# attiny85_transistor.net
KiCad netlist of a schematic drawn in EAGLE
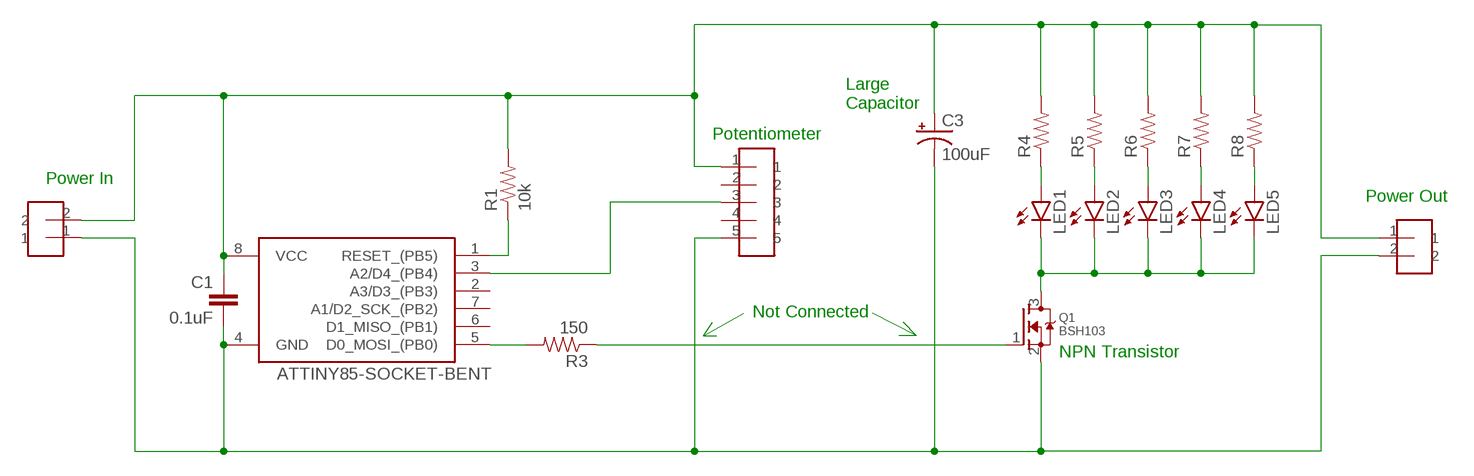
[diagram p0: schematic, sheet 1]

(export (version "E")
  (design (tool "Eeschema 10.0.6"))
  (components
    (comp (ref "C1")
      (value "0.1uF")
      (footprint "eagle-import:0805")
      (libsource (lib "eagle-import") (part "CAP-0805"))
    )
    (comp (ref "C3")
      (value "100uF")
      (footprint "eagle-import:PANASONIC_D")
      (libsource (lib "eagle-import") (part "CAP_POLD"))
    )
    (comp (ref "LED1")
      (value "LED0603")
      (footprint "eagle-import:LED-0603")
      (libsource (lib "eagle-import") (part "LED0603"))
    )
    (comp (ref "LED2")
      (value "LED0603")
      (footprint "eagle-import:LED-0603")
      (libsource (lib "eagle-import") (part "LED0603"))
    )
    (comp (ref "LED3")
      (value "LED0603")
      (footprint "eagle-import:LED-0603")
      (libsource (lib "eagle-import") (part "LED0603"))
    )
    (comp (ref "LED4")
      (value "LED0603")
      (footprint "eagle-import:LED-0603")
      (libsource (lib "eagle-import") (part "LED0603"))
    )
    (comp (ref "LED5")
      (value "LED0603")
      (footprint "eagle-import:LED-0603")
      (libsource (lib "eagle-import") (part "LED0603"))
    )
    (comp (ref "POTENTIOMETER")
      (value "HEADER-5")
      (footprint "eagle-import:HEADER-5")
      (libsource (lib "eagle-import") (part "HEADER-5"))
    )
    (comp (ref "Q1")
      (value "BSH103")
      (footprint "eagle-import:SOT23")
      (libsource (lib "eagle-import") (part "MOSFET-NREFLOW"))
    )
    (comp (ref "R1")
      (value "10k")
      (footprint "eagle-import:0805")
      (libsource (lib "eagle-import") (part "RESISTOR-0805"))
    )
    (comp (ref "R3")
      (value "150")
      (footprint "eagle-import:0805")
      (libsource (lib "eagle-import") (part "RESISTOR-0805"))
    )
    (comp (ref "R4")
      (value "RESISTOR0603")
      (footprint "eagle-import:0603-RES")
      (libsource (lib "eagle-import") (part "RESISTOR0603"))
    )
    (comp (ref "R5")
      (value "RESISTOR0603")
      (footprint "eagle-import:0603-RES")
      (libsource (lib "eagle-import") (part "RESISTOR0603"))
    )
    (comp (ref "R6")
      (value "RESISTOR0603")
      (footprint "eagle-import:0603-RES")
      (libsource (lib "eagle-import") (part "RESISTOR0603"))
    )
    (comp (ref "R7")
      (value "RESISTOR0603")
      (footprint "eagle-import:0603-RES")
      (libsource (lib "eagle-import") (part "RESISTOR0603"))
    )
    (comp (ref "R8")
      (value "RESISTOR0603")
      (footprint "eagle-import:0603-RES")
      (libsource (lib "eagle-import") (part "RESISTOR0603"))
    )
    (comp (ref "U$1")
      (value "ATTINY85-SOCKET-BENT")
      (footprint "eagle-import:SOCKET-8PIN-BENT")
      (libsource (lib "eagle-import") (part "ATTINY85-SOCKET-BENT"))
    )
    (comp (ref "U$2")
      (value "HEADER-2")
      (footprint "eagle-import:HEADER-2")
      (libsource (lib "eagle-import") (part "HEADER-2"))
    )
    (comp (ref "U$3")
      (value "HEADER-2")
      (footprint "eagle-import:HEADER-2")
      (libsource (lib "eagle-import") (part "HEADER-2"))
    )
  )
  (nets
    (net (code "1") (name "Net-(LED1-PadA)") (class "Default")
      (node (ref "LED1") (pin "A") (pinfunction "A_A") (pintype "passive"))
      (node (ref "R4") (pin "1") (pinfunction "1_1") (pintype "passive"))
    )
    (net (code "2") (name "Net-(LED2-PadA)") (class "Default")
      (node (ref "LED2") (pin "A") (pinfunction "A_A") (pintype "passive"))
      (node (ref "R5") (pin "1") (pinfunction "1_1") (pintype "passive"))
    )
    (net (code "3") (name "Net-(LED3-PadA)") (class "Default")
      (node (ref "LED3") (pin "A") (pinfunction "A_A") (pintype "passive"))
      (node (ref "R6") (pin "1") (pinfunction "1_1") (pintype "passive"))
    )
    (net (code "4") (name "Net-(LED4-PadA)") (class "Default")
      (node (ref "LED4") (pin "A") (pinfunction "A_A") (pintype "passive"))
      (node (ref "R7") (pin "1") (pinfunction "1_1") (pintype "passive"))
    )
    (net (code "5") (name "Net-(LED5-PadA)") (class "Default")
      (node (ref "LED5") (pin "A") (pinfunction "A_A") (pintype "passive"))
      (node (ref "R8") (pin "1") (pinfunction "1_1") (pintype "passive"))
    )
    (net (code "6") (name "Net-(Q1-D)") (class "Default")
      (node (ref "LED1") (pin "C") (pinfunction "C_C") (pintype "passive"))
      (node (ref "LED2") (pin "C") (pinfunction "C_C") (pintype "passive"))
      (node (ref "LED3") (pin "C") (pinfunction "C_C") (pintype "passive"))
      (node (ref "LED4") (pin "C") (pinfunction "C_C") (pintype "passive"))
      (node (ref "LED5") (pin "C") (pinfunction "C_C") (pintype "passive"))
      (node (ref "Q1") (pin "3") (pinfunction "D_3") (pintype "bidirectional"))
    )
    (net (code "7") (name "Net-(Q1-G)") (class "Default")
      (node (ref "Q1") (pin "1") (pinfunction "G_1") (pintype "bidirectional"))
      (node (ref "R3") (pin "1") (pinfunction "1_1") (pintype "passive"))
    )
    (net (code "8") (name "Net-(Q1-S)") (class "Default")
      (node (ref "C1") (pin "2") (pinfunction "2_2") (pintype "passive"))
      (node (ref "C3") (pin "-") (pinfunction "-_-") (pintype "passive"))
      (node (ref "POTENTIOMETER") (pin "5") (pinfunction "5_5") (pintype "bidirectional"))
      (node (ref "Q1") (pin "2") (pinfunction "S_2") (pintype "bidirectional"))
      (node (ref "U$1") (pin "4") (pinfunction "GND_4") (pintype "power_in"))
      (node (ref "U$2") (pin "1") (pinfunction "1_1") (pintype "bidirectional"))
      (node (ref "U$3") (pin "2") (pinfunction "2_2") (pintype "bidirectional"))
    )
    (net (code "9") (name "Net-(U$1-A2{slash}D4_(PB4))") (class "Default")
      (node (ref "POTENTIOMETER") (pin "3") (pinfunction "3_3") (pintype "bidirectional"))
      (node (ref "U$1") (pin "3") (pinfunction "A2/D4_(PB4)_3") (pintype "bidirectional"))
    )
    (net (code "10") (name "Net-(U$1-D0_MOSI_(PB0))") (class "Default")
      (node (ref "R3") (pin "2") (pinfunction "2_2") (pintype "passive"))
      (node (ref "U$1") (pin "5") (pinfunction "D0_MOSI_(PB0)_5") (pintype "bidirectional"))
    )
    (net (code "11") (name "Net-(U$1-RESET_(PB5))") (class "Default")
      (node (ref "R1") (pin "1") (pinfunction "1_1") (pintype "passive"))
      (node (ref "U$1") (pin "1") (pinfunction "RESET_(PB5)_1") (pintype "bidirectional"))
    )
    (net (code "12") (name "Net-(U$1-VCC)") (class "Default")
      (node (ref "C1") (pin "1") (pinfunction "1_1") (pintype "passive"))
      (node (ref "C3") (pin "+") (pinfunction "+_+") (pintype "passive"))
      (node (ref "POTENTIOMETER") (pin "1") (pinfunction "1_1") (pintype "bidirectional"))
      (node (ref "R1") (pin "2") (pinfunction "2_2") (pintype "passive"))
      (node (ref "R4") (pin "2") (pinfunction "2_2") (pintype "passive"))
      (node (ref "R5") (pin "2") (pinfunction "2_2") (pintype "passive"))
      (node (ref "R6") (pin "2") (pinfunction "2_2") (pintype "passive"))
      (node (ref "R7") (pin "2") (pinfunction "2_2") (pintype "passive"))
      (node (ref "R8") (pin "2") (pinfunction "2_2") (pintype "passive"))
      (node (ref "U$1") (pin "8") (pinfunction "VCC_8") (pintype "power_in"))
      (node (ref "U$2") (pin "2") (pinfunction "2_2") (pintype "bidirectional"))
      (node (ref "U$3") (pin "1") (pinfunction "1_1") (pintype "bidirectional"))
    )
    (net (code "13") (name "unconnected-(POTENTIOMETER-Pad2)") (class "Default")
      (node (ref "POTENTIOMETER") (pin "2") (pinfunction "2_2") (pintype "bidirectional"))
    )
    (net (code "14") (name "unconnected-(POTENTIOMETER-Pad4)") (class "Default")
      (node (ref "POTENTIOMETER") (pin "4") (pinfunction "4_4") (pintype "bidirectional"))
    )
    (net (code "15") (name "unconnected-(U$1-A1{slash}D2_SCK_(PB2)-Pad7)") (class "Default")
      (node (ref "U$1") (pin "7") (pinfunction "A1/D2_SCK_(PB2)_7") (pintype "bidirectional"))
    )
    (net (code "16") (name "unconnected-(U$1-A3{slash}D3_(PB3)-Pad2)") (class "Default")
      (node (ref "U$1") (pin "2") (pinfunction "A3/D3_(PB3)_2") (pintype "bidirectional"))
    )
    (net (code "17") (name "unconnected-(U$1-D1_MISO_(PB1)-Pad6)") (class "Default")
      (node (ref "U$1") (pin "6") (pinfunction "D1_MISO_(PB1)_6") (pintype "bidirectional"))
    )
  )
)
